# 03-CPU_Core.net
KiCad netlist of a schematic drawn in Altium Designer
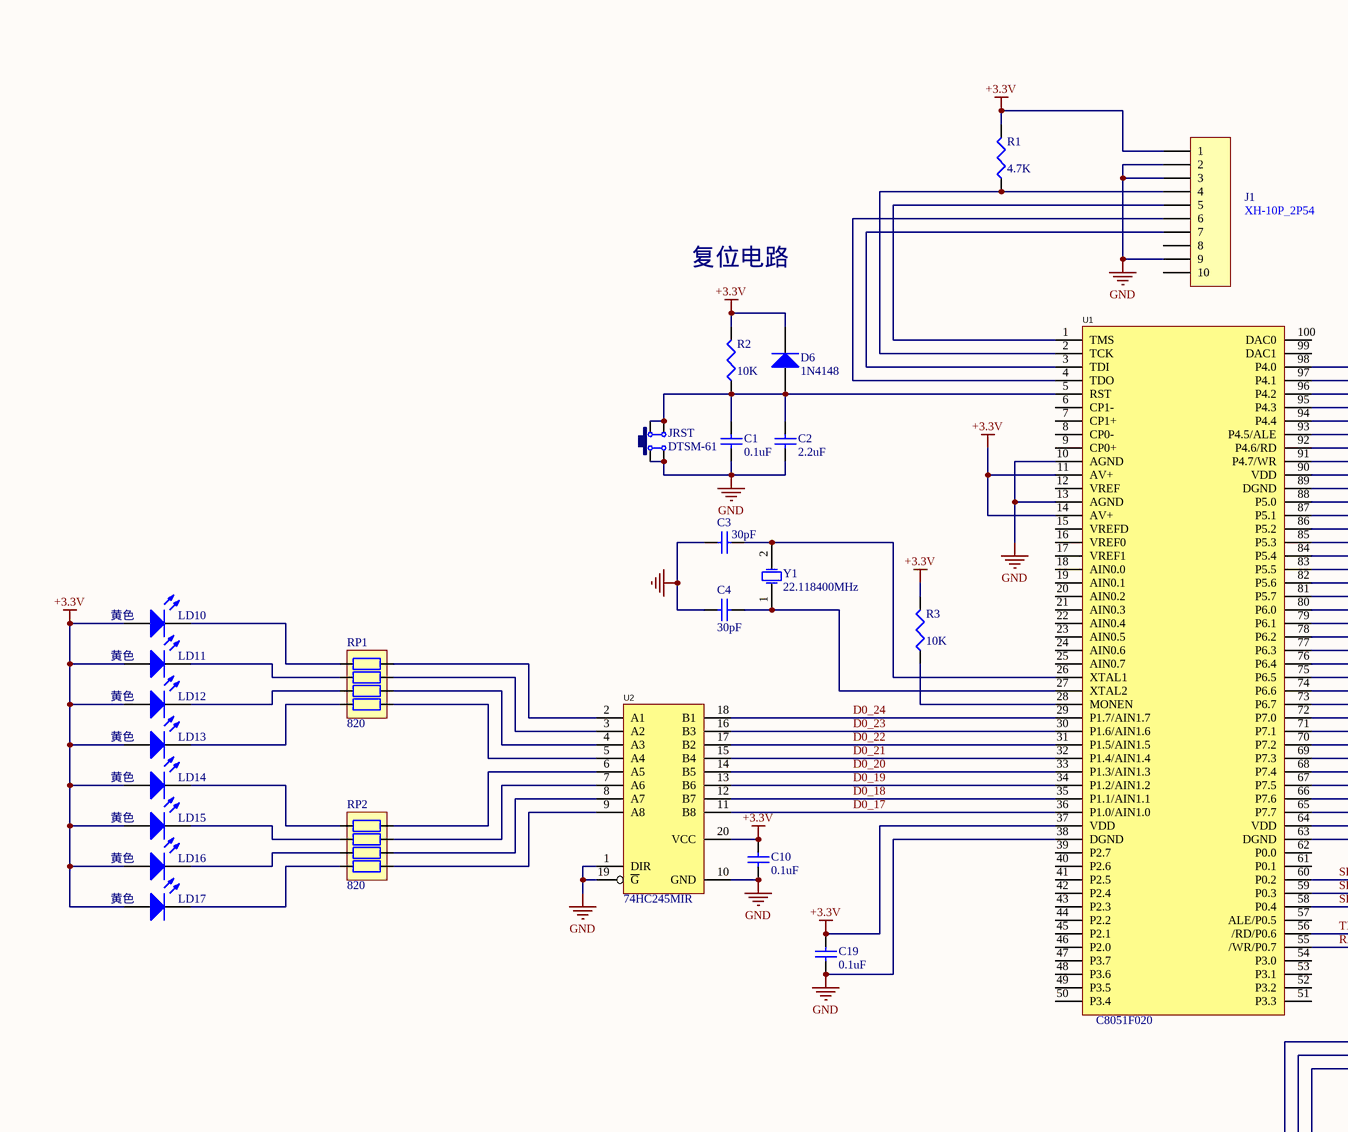
[diagram p0: 03-CPU Core.SchDoc, left]
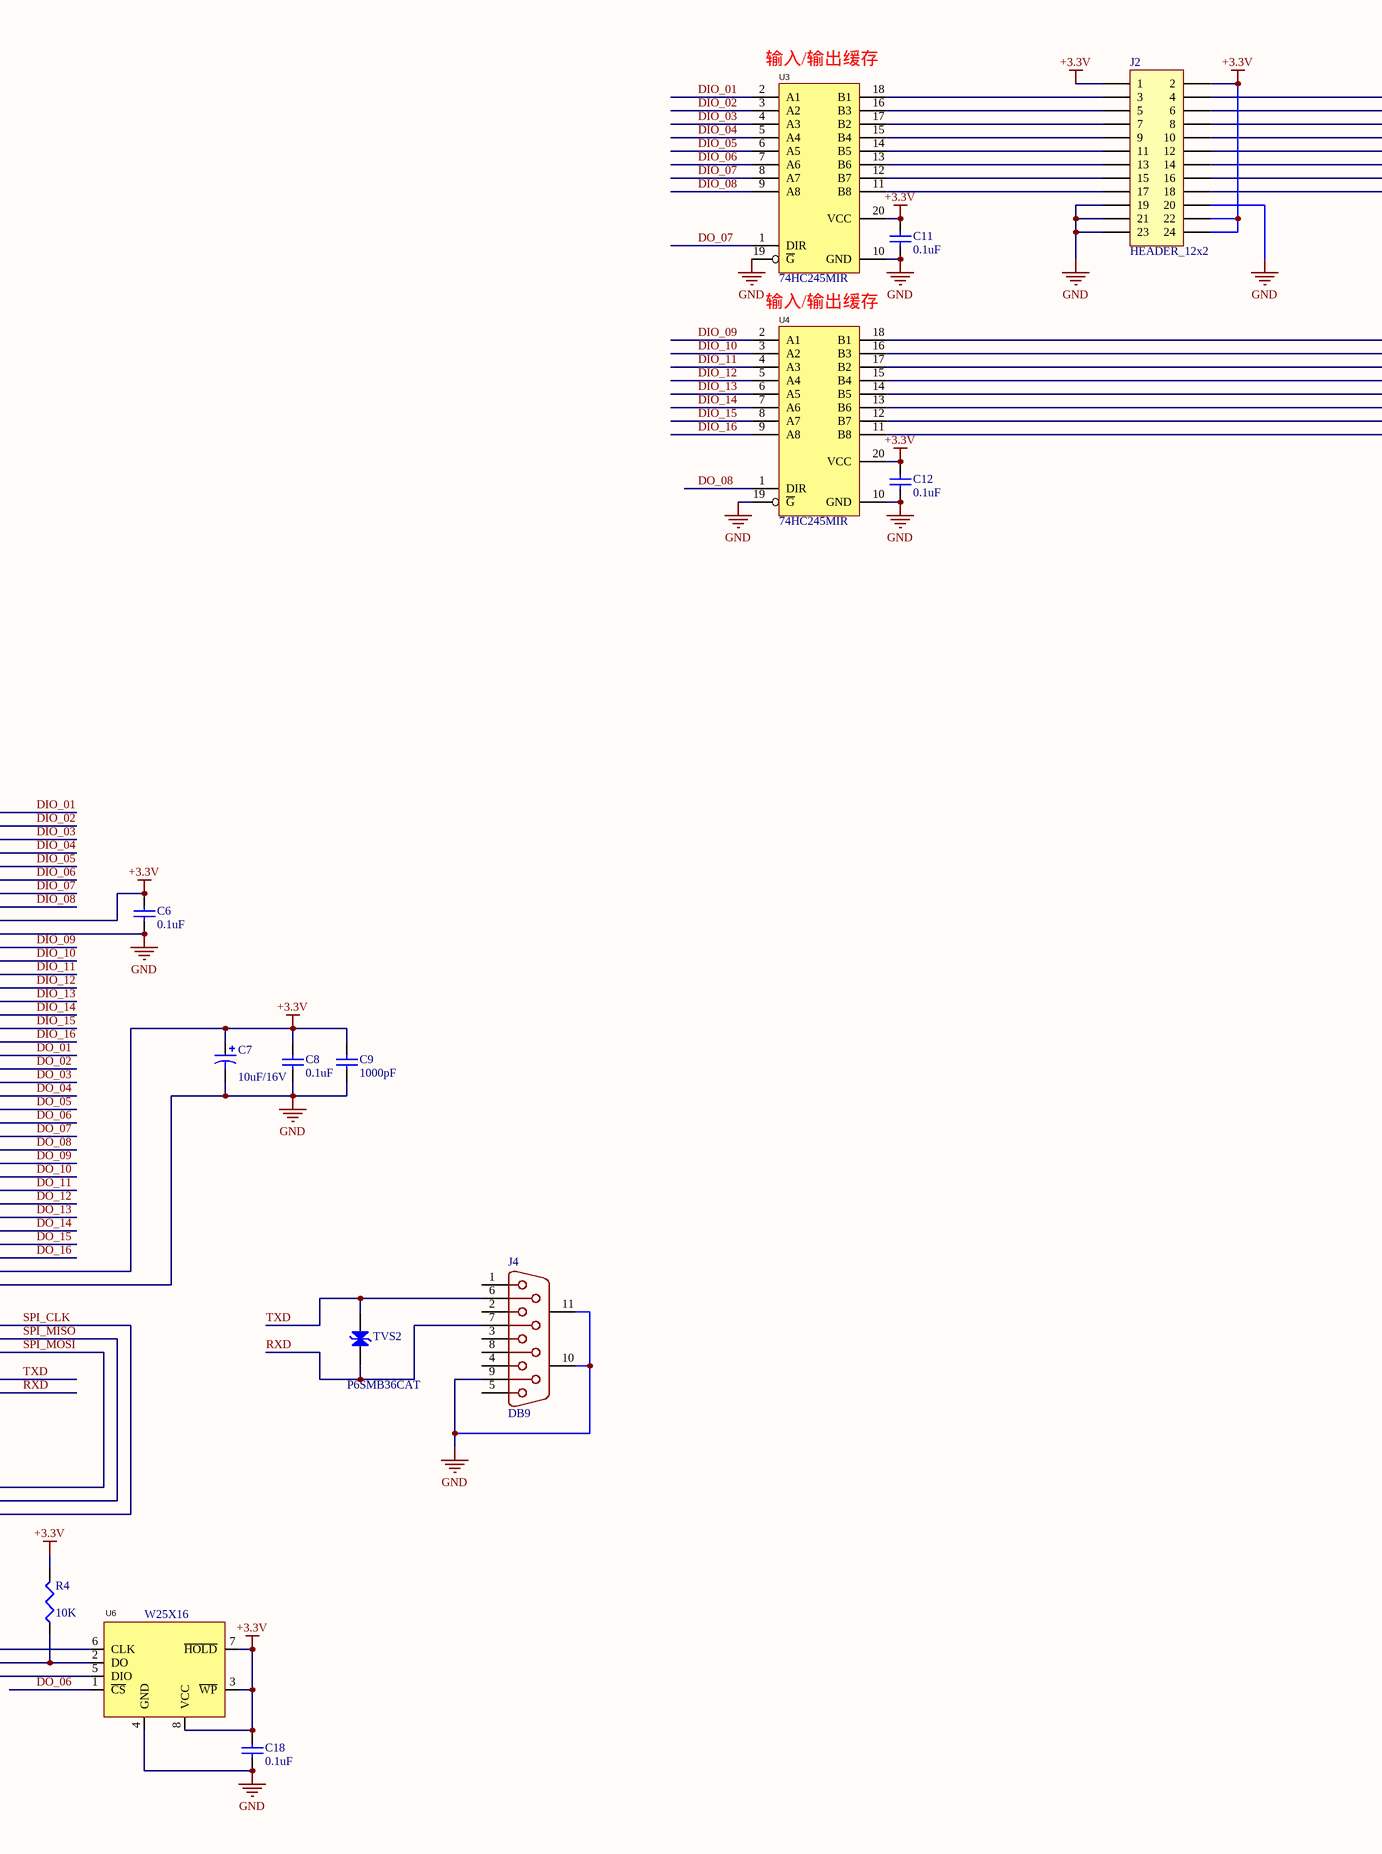
[diagram p1: 03-CPU Core.SchDoc, right]

(export (version "E")
  (design (tool "Eeschema 10.0.6"))
  (components
    (comp (ref "C1")
      (value "0.1uF")
      (footprint "C0805")
      (description "Capacitor")
      (fields (field (name "Comment") "Cap") (field (name "PUBLISHER") "Altium Limited"))
      (libsource (lib "Miscellaneous Devices") (part "Cap"))
    )
    (comp (ref "C2")
      (value "2.2uF")
      (footprint "C0805")
      (description "Capacitor")
      (fields (field (name "Comment") "Cap") (field (name "PUBLISHER") "Altium Limited"))
      (libsource (lib "Miscellaneous Devices") (part "Cap"))
    )
    (comp (ref "C3")
      (value "30pF")
      (footprint "C0805")
      (description "Capacitor")
      (fields (field (name "Comment") "Cap") (field (name "PUBLISHER") "Altium Limited"))
      (libsource (lib "Miscellaneous Devices") (part "Cap"))
    )
    (comp (ref "C4")
      (value "30pF")
      (footprint "C0805")
      (description "Capacitor")
      (fields (field (name "Comment") "Cap") (field (name "PUBLISHER") "Altium Limited"))
      (libsource (lib "Miscellaneous Devices") (part "Cap"))
    )
    (comp (ref "C6")
      (value "0.1uF")
      (footprint "C0805")
      (description "Capacitor")
      (fields (field (name "Comment") "Cap") (field (name "PUBLISHER") "Altium Limited"))
      (libsource (lib "Miscellaneous Devices") (part "Cap"))
    )
    (comp (ref "C7")
      (value "10uF/16V")
      (footprint "C3216")
      (description "Polarized Capacitor (Radial)")
      (fields (field (name "Comment") "Cap Pol1") (field (name "PUBLISHER") "Altium Limited"))
      (libsource (lib "Miscellaneous Devices") (part "Cap Pol1"))
    )
    (comp (ref "C8")
      (value "0.1uF")
      (footprint "C0805")
      (description "Capacitor")
      (fields (field (name "Comment") "Cap") (field (name "PUBLISHER") "Altium Limited"))
      (libsource (lib "Miscellaneous Devices") (part "Cap"))
    )
    (comp (ref "C9")
      (value "1000pF")
      (footprint "C0805")
      (description "Capacitor")
      (fields (field (name "Comment") "Cap") (field (name "PUBLISHER") "Altium Limited"))
      (libsource (lib "Miscellaneous Devices") (part "Cap"))
    )
    (comp (ref "C10")
      (value "0.1uF")
      (footprint "C0805")
      (description "Capacitor")
      (fields (field (name "Comment") "Cap") (field (name "PUBLISHER") "Altium Limited"))
      (libsource (lib "Miscellaneous Devices") (part "Cap"))
    )
    (comp (ref "C11")
      (value "0.1uF")
      (footprint "C0805")
      (description "Capacitor")
      (fields (field (name "Comment") "Cap") (field (name "PUBLISHER") "Altium Limited"))
      (libsource (lib "Miscellaneous Devices") (part "Cap"))
    )
    (comp (ref "C12")
      (value "0.1uF")
      (footprint "C0805")
      (description "Capacitor")
      (fields (field (name "Comment") "Cap") (field (name "PUBLISHER") "Altium Limited"))
      (libsource (lib "Miscellaneous Devices") (part "Cap"))
    )
    (comp (ref "C18")
      (value "0.1uF")
      (footprint "C0805")
      (description "Capacitor")
      (fields (field (name "Comment") "Cap") (field (name "PUBLISHER") "Altium Limited"))
      (libsource (lib "Miscellaneous Devices") (part "Cap"))
    )
    (comp (ref "C19")
      (value "0.1uF")
      (footprint "C0805")
      (description "Capacitor")
      (fields (field (name "Comment") "Cap") (field (name "PUBLISHER") "Altium Limited"))
      (libsource (lib "Miscellaneous Devices") (part "Cap"))
    )
    (comp (ref "D6")
      (value "1N4148")
      (footprint "FR107W")
      (description "Default Diode")
      (fields (field (name "PUBLISHER") "Altium Limited"))
      (libsource (lib "Miscellaneous Devices") (part "Diode"))
    )
    (comp (ref "J1")
      (value "XH-10P_2P54")
      (footprint "XH-10P_2P54")
      (description "Header, 10-Pin")
      (fields (field (name "PUBLISHER") "Altium Limited"))
      (libsource (lib "Miscellaneous Connectors") (part "Header 10"))
    )
    (comp (ref "J2")
      (value "HEADER_12x2")
      (footprint "HEADER_12x2")
      (description "Header, 12-Pin, Dual row")
      (fields (field (name "PUBLISHER") "Altium Limited"))
      (libsource (lib "Miscellaneous Connectors") (part "Header 12X2"))
    )
    (comp (ref "J4") (value "DB9") (footprint "DB9") (libsource (lib "SCHLIB") (part "DB9")))
    (comp (ref "JRST") (value "DTSM-61") (footprint "DISM-61") (libsource (lib "SCHLIB") (part "DTSM-61")))
    (comp (ref "LD10")
      (value "黄色")
      (footprint "LED0805")
      (description "Typical INFRARED GaAs LED")
      (fields (field (name "PUBLISHER") "Altium Limited"))
      (libsource (lib "Miscellaneous Devices") (part "LED0"))
    )
    (comp (ref "LD11")
      (value "黄色")
      (footprint "LED0805")
      (description "Typical INFRARED GaAs LED")
      (fields (field (name "PUBLISHER") "Altium Limited"))
      (libsource (lib "Miscellaneous Devices") (part "LED0"))
    )
    (comp (ref "LD12")
      (value "黄色")
      (footprint "LED0805")
      (description "Typical INFRARED GaAs LED")
      (fields (field (name "PUBLISHER") "Altium Limited"))
      (libsource (lib "Miscellaneous Devices") (part "LED0"))
    )
    (comp (ref "LD13")
      (value "黄色")
      (footprint "LED0805")
      (description "Typical INFRARED GaAs LED")
      (fields (field (name "PUBLISHER") "Altium Limited"))
      (libsource (lib "Miscellaneous Devices") (part "LED0"))
    )
    (comp (ref "LD14")
      (value "黄色")
      (footprint "LED0805")
      (description "Typical INFRARED GaAs LED")
      (fields (field (name "PUBLISHER") "Altium Limited"))
      (libsource (lib "Miscellaneous Devices") (part "LED0"))
    )
    (comp (ref "LD15")
      (value "黄色")
      (footprint "LED0805")
      (description "Typical INFRARED GaAs LED")
      (fields (field (name "PUBLISHER") "Altium Limited"))
      (libsource (lib "Miscellaneous Devices") (part "LED0"))
    )
    (comp (ref "LD16")
      (value "黄色")
      (footprint "LED0805")
      (description "Typical INFRARED GaAs LED")
      (fields (field (name "PUBLISHER") "Altium Limited"))
      (libsource (lib "Miscellaneous Devices") (part "LED0"))
    )
    (comp (ref "LD17")
      (value "黄色")
      (footprint "LED0805")
      (description "Typical INFRARED GaAs LED")
      (fields (field (name "PUBLISHER") "Altium Limited"))
      (libsource (lib "Miscellaneous Devices") (part "LED0"))
    )
    (comp (ref "R1")
      (value "4.7K")
      (footprint "R0805")
      (description "Resistor")
      (fields (field (name "Comment") "Res3") (field (name "PUBLISHER") "Altium Limited"))
      (libsource (lib "Miscellaneous Devices") (part "Res3"))
    )
    (comp (ref "R2")
      (value "10K")
      (footprint "R0805")
      (description "Resistor")
      (fields (field (name "Comment") "Res3") (field (name "PUBLISHER") "Altium Limited"))
      (libsource (lib "Miscellaneous Devices") (part "Res3"))
    )
    (comp (ref "R3")
      (value "10K")
      (footprint "R0805")
      (description "Resistor")
      (fields (field (name "Comment") "Res3") (field (name "PUBLISHER") "Altium Limited"))
      (libsource (lib "Miscellaneous Devices") (part "Res3"))
    )
    (comp (ref "R4")
      (value "10K")
      (footprint "R0805")
      (description "Resistor")
      (fields (field (name "Comment") "Res3") (field (name "PUBLISHER") "Altium Limited"))
      (libsource (lib "Miscellaneous Devices") (part "Res3"))
    )
    (comp (ref "RP1") (value "820") (footprint "RP") (libsource (lib "SCHLIB") (part "RP 820")))
    (comp (ref "RP2") (value "820") (footprint "RP") (libsource (lib "SCHLIB") (part "RP 820")))
    (comp (ref "TVS2") (value "P6SMB36CAT") (footprint "TVS") (libsource (lib "SCHLIB") (part "SMD")))
    (comp (ref "U1")
      (value "C8051F020")
      (footprint "TQFP-100")
      (fields
        (field (name "MANUFACTURER") "SKYWORKS/SILICON LABS(芯科)")
        (field (name "MANUFACTURER PART") "C8051F020-GQR")
      )
      (libsource (lib "C8051F020") (part "C8051F020"))
    )
    (comp (ref "U2")
      (value "74HC245MIR")
      (footprint "SSOP-20")
      (fields (field (name "MANUFACTURER") "Nexperia(安世)") (field (name "MANUFACTURER PART") "74HC245PW,118"))
      (libsource (lib "C8051F020") (part "74HC245MIR"))
    )
    (comp (ref "U3")
      (value "74HC245MIR")
      (footprint "SSOP-20")
      (fields (field (name "MANUFACTURER") "Nexperia(安世)") (field (name "MANUFACTURER PART") "74HC245PW,118"))
      (libsource (lib "C8051F020") (part "74HC245MIR"))
    )
    (comp (ref "U4")
      (value "74HC245MIR")
      (footprint "SSOP-20")
      (fields (field (name "MANUFACTURER") "Nexperia(安世)") (field (name "MANUFACTURER PART") "74HC245PW,118"))
      (libsource (lib "C8051F020") (part "74HC245MIR"))
    )
    (comp (ref "U6")
      (value "W25X16")
      (footprint "SOIC-8")
      (fields (field (name "MANUFACTURER") "WINBOND(华邦)") (field (name "MANUFACTURER PART") "W25X16VSSIG"))
      (libsource (lib "C8051F020") (part "W25X16"))
    )
    (comp (ref "Y1")
      (value "22.118400MHz")
      (footprint "HC-49")
      (description "Crystal Oscillator")
      (fields (field (name "PUBLISHER") "Altium Limited"))
      (libsource (lib "Miscellaneous Devices") (part "XTAL"))
    )
  )
  (nets
    (net (code "1") (name "+3.3V") (class "Default")
      (node (ref "C10") (pin "2") (pinfunction "2_2") (pintype "passive"))
      (node (ref "C11") (pin "2") (pinfunction "2_2") (pintype "passive"))
      (node (ref "C12") (pin "2") (pinfunction "2_2") (pintype "passive"))
      (node (ref "C18") (pin "2") (pinfunction "2_2") (pintype "passive"))
      (node (ref "C19") (pin "2") (pinfunction "2_2") (pintype "passive"))
      (node (ref "C6") (pin "2") (pinfunction "2_2") (pintype "passive"))
      (node (ref "C7") (pin "1") (pinfunction "1_1") (pintype "passive"))
      (node (ref "C8") (pin "2") (pinfunction "2_2") (pintype "passive"))
      (node (ref "C9") (pin "2") (pinfunction "2_2") (pintype "passive"))
      (node (ref "D6") (pin "2") (pinfunction "K_2") (pintype "passive"))
      (node (ref "J1") (pin "1") (pinfunction "1_1") (pintype "passive"))
      (node (ref "J2") (pin "1") (pinfunction "1_1") (pintype "passive"))
      (node (ref "J2") (pin "2") (pinfunction "2_2") (pintype "passive"))
      (node (ref "J2") (pin "22") (pinfunction "22_22") (pintype "passive"))
      (node (ref "J2") (pin "24") (pinfunction "24_24") (pintype "passive"))
      (node (ref "LD10") (pin "1") (pinfunction "A_1") (pintype "passive"))
      (node (ref "LD11") (pin "1") (pinfunction "A_1") (pintype "passive"))
      (node (ref "LD12") (pin "1") (pinfunction "A_1") (pintype "passive"))
      (node (ref "LD13") (pin "1") (pinfunction "A_1") (pintype "passive"))
      (node (ref "LD14") (pin "1") (pinfunction "A_1") (pintype "passive"))
      (node (ref "LD15") (pin "1") (pinfunction "A_1") (pintype "passive"))
      (node (ref "LD16") (pin "1") (pinfunction "A_1") (pintype "passive"))
      (node (ref "LD17") (pin "1") (pinfunction "A_1") (pintype "passive"))
      (node (ref "R1") (pin "2") (pinfunction "2_2") (pintype "passive"))
      (node (ref "R2") (pin "2") (pinfunction "2_2") (pintype "passive"))
      (node (ref "R3") (pin "2") (pinfunction "2_2") (pintype "passive"))
      (node (ref "R4") (pin "2") (pinfunction "2_2") (pintype "passive"))
      (node (ref "U1") (pin "11") (pinfunction "AV+_11") (pintype "passive"))
      (node (ref "U1") (pin "14") (pinfunction "AV+_14") (pintype "passive"))
      (node (ref "U1") (pin "37") (pinfunction "VDD_37") (pintype "passive"))
      (node (ref "U1") (pin "64") (pinfunction "VDD_64") (pintype "passive"))
      (node (ref "U1") (pin "90") (pinfunction "VDD_90") (pintype "passive"))
      (node (ref "U2") (pin "20") (pinfunction "VCC_20") (pintype "passive"))
      (node (ref "U3") (pin "20") (pinfunction "VCC_20") (pintype "passive"))
      (node (ref "U4") (pin "20") (pinfunction "VCC_20") (pintype "passive"))
      (node (ref "U6") (pin "3") (pinfunction "~{WP}_3") (pintype "passive"))
      (node (ref "U6") (pin "7") (pinfunction "~{HOLD}_7") (pintype "passive"))
      (node (ref "U6") (pin "8") (pinfunction "VCC_8") (pintype "passive"))
    )
    (net (code "2") (name "/D0_17") (class "Default")
      (node (ref "U1") (pin "36") (pinfunction "P1.0/AIN1.0_36") (pintype "passive"))
      (node (ref "U2") (pin "11") (pinfunction "B8_11") (pintype "passive"))
    )
    (net (code "3") (name "/D0_18") (class "Default")
      (node (ref "U1") (pin "35") (pinfunction "P1.1/AIN1.1_35") (pintype "passive"))
      (node (ref "U2") (pin "12") (pinfunction "B7_12") (pintype "passive"))
    )
    (net (code "4") (name "/D0_19") (class "Default")
      (node (ref "U1") (pin "34") (pinfunction "P1.2/AIN1.2_34") (pintype "passive"))
      (node (ref "U2") (pin "13") (pinfunction "B6_13") (pintype "passive"))
    )
    (net (code "5") (name "/D0_20") (class "Default")
      (node (ref "U1") (pin "33") (pinfunction "P1.3/AIN1.3_33") (pintype "passive"))
      (node (ref "U2") (pin "14") (pinfunction "B5_14") (pintype "passive"))
    )
    (net (code "6") (name "/D0_21") (class "Default")
      (node (ref "U1") (pin "32") (pinfunction "P1.4/AIN1.4_32") (pintype "passive"))
      (node (ref "U2") (pin "15") (pinfunction "B4_15") (pintype "passive"))
    )
    (net (code "7") (name "/D0_22") (class "Default")
      (node (ref "U1") (pin "31") (pinfunction "P1.5/AIN1.5_31") (pintype "passive"))
      (node (ref "U2") (pin "17") (pinfunction "B2_17") (pintype "passive"))
    )
    (net (code "8") (name "/D0_23") (class "Default")
      (node (ref "U1") (pin "30") (pinfunction "P1.6/AIN1.6_30") (pintype "passive"))
      (node (ref "U2") (pin "16") (pinfunction "B3_16") (pintype "passive"))
    )
    (net (code "9") (name "/D0_24") (class "Default")
      (node (ref "U1") (pin "29") (pinfunction "P1.7/AIN1.7_29") (pintype "passive"))
      (node (ref "U2") (pin "18") (pinfunction "B1_18") (pintype "passive"))
    )
    (net (code "10") (name "/DIO_01") (class "Default")
      (node (ref "U1") (pin "98") (pinfunction "P4.0_98") (pintype "passive"))
      (node (ref "U3") (pin "2") (pinfunction "A1_2") (pintype "passive"))
    )
    (net (code "11") (name "/DIO_02") (class "Default")
      (node (ref "U1") (pin "97") (pinfunction "P4.1_97") (pintype "passive"))
      (node (ref "U3") (pin "3") (pinfunction "A2_3") (pintype "passive"))
    )
    (net (code "12") (name "/DIO_03") (class "Default")
      (node (ref "U1") (pin "96") (pinfunction "P4.2_96") (pintype "passive"))
      (node (ref "U3") (pin "4") (pinfunction "A3_4") (pintype "passive"))
    )
    (net (code "13") (name "/DIO_04") (class "Default")
      (node (ref "U1") (pin "95") (pinfunction "P4.3_95") (pintype "passive"))
      (node (ref "U3") (pin "5") (pinfunction "A4_5") (pintype "passive"))
    )
    (net (code "14") (name "/DIO_05") (class "Default")
      (node (ref "U1") (pin "94") (pinfunction "P4.4_94") (pintype "passive"))
      (node (ref "U3") (pin "6") (pinfunction "A5_6") (pintype "passive"))
    )
    (net (code "15") (name "/DIO_06") (class "Default")
      (node (ref "U1") (pin "93") (pinfunction "P4.5/ALE_93") (pintype "passive"))
      (node (ref "U3") (pin "7") (pinfunction "A6_7") (pintype "passive"))
    )
    (net (code "16") (name "/DIO_07") (class "Default")
      (node (ref "U1") (pin "92") (pinfunction "P4.6/RD_92") (pintype "passive"))
      (node (ref "U3") (pin "8") (pinfunction "A7_8") (pintype "passive"))
    )
    (net (code "17") (name "/DIO_08") (class "Default")
      (node (ref "U1") (pin "91") (pinfunction "P4.7/WR_91") (pintype "passive"))
      (node (ref "U3") (pin "9") (pinfunction "A8_9") (pintype "passive"))
    )
    (net (code "18") (name "/DIO_09") (class "Default")
      (node (ref "U1") (pin "88") (pinfunction "P5.0_88") (pintype "passive"))
      (node (ref "U4") (pin "2") (pinfunction "A1_2") (pintype "passive"))
    )
    (net (code "19") (name "/DIO_10") (class "Default")
      (node (ref "U1") (pin "87") (pinfunction "P5.1_87") (pintype "passive"))
      (node (ref "U4") (pin "3") (pinfunction "A2_3") (pintype "passive"))
    )
    (net (code "20") (name "/DIO_11") (class "Default")
      (node (ref "U1") (pin "86") (pinfunction "P5.2_86") (pintype "passive"))
      (node (ref "U4") (pin "4") (pinfunction "A3_4") (pintype "passive"))
    )
    (net (code "21") (name "/DIO_12") (class "Default")
      (node (ref "U1") (pin "85") (pinfunction "P5.3_85") (pintype "passive"))
      (node (ref "U4") (pin "5") (pinfunction "A4_5") (pintype "passive"))
    )
    (net (code "22") (name "/DIO_13") (class "Default")
      (node (ref "U1") (pin "84") (pinfunction "P5.4_84") (pintype "passive"))
      (node (ref "U4") (pin "6") (pinfunction "A5_6") (pintype "passive"))
    )
    (net (code "23") (name "/DIO_14") (class "Default")
      (node (ref "U1") (pin "83") (pinfunction "P5.5_83") (pintype "passive"))
      (node (ref "U4") (pin "7") (pinfunction "A6_7") (pintype "passive"))
    )
    (net (code "24") (name "/DIO_15") (class "Default")
      (node (ref "U1") (pin "82") (pinfunction "P5.6_82") (pintype "passive"))
      (node (ref "U4") (pin "8") (pinfunction "A7_8") (pintype "passive"))
    )
    (net (code "25") (name "/DIO_16") (class "Default")
      (node (ref "U1") (pin "81") (pinfunction "P5.7_81") (pintype "passive"))
      (node (ref "U4") (pin "9") (pinfunction "A8_9") (pintype "passive"))
    )
    (net (code "26") (name "/DO_01") (class "Default")
      (node (ref "U1") (pin "80") (pinfunction "P6.0_80") (pintype "passive"))
    )
    (net (code "27") (name "/DO_02") (class "Default")
      (node (ref "U1") (pin "79") (pinfunction "P6.1_79") (pintype "passive"))
    )
    (net (code "28") (name "/DO_03") (class "Default")
      (node (ref "U1") (pin "78") (pinfunction "P6.2_78") (pintype "passive"))
    )
    (net (code "29") (name "/DO_04") (class "Default")
      (node (ref "U1") (pin "77") (pinfunction "P6.3_77") (pintype "passive"))
    )
    (net (code "30") (name "/DO_05") (class "Default")
      (node (ref "U1") (pin "76") (pinfunction "P6.4_76") (pintype "passive"))
    )
    (net (code "31") (name "/DO_06") (class "Default")
      (node (ref "U1") (pin "75") (pinfunction "P6.5_75") (pintype "passive"))
      (node (ref "U6") (pin "1") (pinfunction "~{CS}_1") (pintype "passive"))
    )
    (net (code "32") (name "/DO_07") (class "Default")
      (node (ref "U1") (pin "74") (pinfunction "P6.6_74") (pintype "passive"))
      (node (ref "U3") (pin "1") (pinfunction "DIR_1") (pintype "passive"))
    )
    (net (code "33") (name "/DO_08") (class "Default")
      (node (ref "U1") (pin "73") (pinfunction "P6.7_73") (pintype "passive"))
      (node (ref "U4") (pin "1") (pinfunction "DIR_1") (pintype "passive"))
    )
    (net (code "34") (name "/DO_09") (class "Default")
      (node (ref "U1") (pin "72") (pinfunction "P7.0_72") (pintype "passive"))
    )
    (net (code "35") (name "/DO_10") (class "Default")
      (node (ref "U1") (pin "71") (pinfunction "P7.1_71") (pintype "passive"))
    )
    (net (code "36") (name "/DO_11") (class "Default")
      (node (ref "U1") (pin "70") (pinfunction "P7.2_70") (pintype "passive"))
    )
    (net (code "37") (name "/DO_12") (class "Default")
      (node (ref "U1") (pin "69") (pinfunction "P7.3_69") (pintype "passive"))
    )
    (net (code "38") (name "/DO_13") (class "Default")
      (node (ref "U1") (pin "68") (pinfunction "P7.4_68") (pintype "passive"))
    )
    (net (code "39") (name "/DO_14") (class "Default")
      (node (ref "U1") (pin "67") (pinfunction "P7.5_67") (pintype "passive"))
    )
    (net (code "40") (name "/DO_15") (class "Default")
      (node (ref "U1") (pin "66") (pinfunction "P7.6_66") (pintype "passive"))
    )
    (net (code "41") (name "/DO_16") (class "Default")
      (node (ref "U1") (pin "65") (pinfunction "P7.7_65") (pintype "passive"))
    )
    (net (code "42") (name "/RXD") (class "Default")
      (node (ref "J4") (pin "7") (pinfunction "7_7") (pintype "passive"))
      (node (ref "TVS2") (pin "2") (pinfunction "K_2") (pintype "passive"))
      (node (ref "U1") (pin "55") (pinfunction "/WR/P0.7_55") (pintype "passive"))
    )
    (net (code "43") (name "/SPI_CLK") (class "Default")
      (node (ref "U1") (pin "60") (pinfunction "P0.2_60") (pintype "passive"))
      (node (ref "U6") (pin "6") (pinfunction "CLK_6") (pintype "passive"))
    )
    (net (code "44") (name "/SPI_MISO") (class "Default")
      (node (ref "R4") (pin "1") (pinfunction "1_1") (pintype "passive"))
      (node (ref "U1") (pin "59") (pinfunction "P0.3_59") (pintype "passive"))
      (node (ref "U6") (pin "2") (pinfunction "DO_2") (pintype "passive"))
    )
    (net (code "45") (name "/SPI_MOSI") (class "Default")
      (node (ref "U1") (pin "58") (pinfunction "P0.4_58") (pintype "passive"))
      (node (ref "U6") (pin "5") (pinfunction "DIO_5") (pintype "passive"))
    )
    (net (code "46") (name "/TXD") (class "Default")
      (node (ref "J4") (pin "6") (pinfunction "6_6") (pintype "passive"))
      (node (ref "TVS2") (pin "1") (pinfunction "A_1") (pintype "passive"))
      (node (ref "U1") (pin "56") (pinfunction "/RD/P0.6_56") (pintype "passive"))
    )
    (net (code "47") (name "GND") (class "Default")
      (node (ref "C1") (pin "2") (pinfunction "2_2") (pintype "passive"))
      (node (ref "C10") (pin "1") (pinfunction "1_1") (pintype "passive"))
      (node (ref "C11") (pin "1") (pinfunction "1_1") (pintype "passive"))
      (node (ref "C12") (pin "1") (pinfunction "1_1") (pintype "passive"))
      (node (ref "C18") (pin "1") (pinfunction "1_1") (pintype "passive"))
      (node (ref "C19") (pin "1") (pinfunction "1_1") (pintype "passive"))
      (node (ref "C2") (pin "2") (pinfunction "2_2") (pintype "passive"))
      (node (ref "C3") (pin "1") (pinfunction "1_1") (pintype "passive"))
      (node (ref "C4") (pin "1") (pinfunction "1_1") (pintype "passive"))
      (node (ref "C6") (pin "1") (pinfunction "1_1") (pintype "passive"))
      (node (ref "C7") (pin "2") (pinfunction "2_2") (pintype "passive"))
      (node (ref "C8") (pin "1") (pinfunction "1_1") (pintype "passive"))
      (node (ref "C9") (pin "1") (pinfunction "1_1") (pintype "passive"))
      (node (ref "J1") (pin "2") (pinfunction "2_2") (pintype "passive"))
      (node (ref "J1") (pin "3") (pinfunction "3_3") (pintype "passive"))
      (node (ref "J1") (pin "9") (pinfunction "9_9") (pintype "passive"))
      (node (ref "J2") (pin "19") (pinfunction "19_19") (pintype "passive"))
      (node (ref "J2") (pin "20") (pinfunction "20_20") (pintype "passive"))
      (node (ref "J2") (pin "21") (pinfunction "21_21") (pintype "passive"))
      (node (ref "J2") (pin "23") (pinfunction "23_23") (pintype "passive"))
      (node (ref "J4") (pin "10") (pinfunction "MH1_10") (pintype "passive"))
      (node (ref "J4") (pin "11") (pinfunction "MH2_11") (pintype "passive"))
      (node (ref "J4") (pin "9") (pinfunction "9_9") (pintype "passive"))
      (node (ref "JRST") (pin "1") (pinfunction "1_1") (pintype "passive"))
      (node (ref "JRST") (pin "4") (pinfunction "4_4") (pintype "passive"))
      (node (ref "U1") (pin "10") (pinfunction "AGND_10") (pintype "passive"))
      (node (ref "U1") (pin "13") (pinfunction "AGND_13") (pintype "passive"))
      (node (ref "U1") (pin "38") (pinfunction "DGND_38") (pintype "passive"))
      (node (ref "U1") (pin "63") (pinfunction "DGND_63") (pintype "passive"))
      (node (ref "U1") (pin "89") (pinfunction "DGND_89") (pintype "passive"))
      (node (ref "U2") (pin "1") (pinfunction "DIR_1") (pintype "passive"))
      (node (ref "U2") (pin "10") (pinfunction "GND_10") (pintype "passive"))
      (node (ref "U2") (pin "19") (pinfunction "~{G}_19") (pintype "passive"))
      (node (ref "U3") (pin "10") (pinfunction "GND_10") (pintype "passive"))
      (node (ref "U3") (pin "19") (pinfunction "~{G}_19") (pintype "passive"))
      (node (ref "U4") (pin "10") (pinfunction "GND_10") (pintype "passive"))
      (node (ref "U4") (pin "19") (pinfunction "~{G}_19") (pintype "passive"))
      (node (ref "U6") (pin "4") (pinfunction "GND_4") (pintype "passive"))
    )
    (net (code "48") (name "Net-(D6-A)") (class "Default")
      (node (ref "C1") (pin "1") (pinfunction "1_1") (pintype "passive"))
      (node (ref "C2") (pin "1") (pinfunction "1_1") (pintype "passive"))
      (node (ref "D6") (pin "1") (pinfunction "A_1") (pintype "passive"))
      (node (ref "JRST") (pin "2") (pinfunction "2_2") (pintype "passive"))
      (node (ref "JRST") (pin "3") (pinfunction "3_3") (pintype "passive"))
      (node (ref "R2") (pin "1") (pinfunction "1_1") (pintype "passive"))
      (node (ref "U1") (pin "5") (pinfunction "RST_5") (pintype "passive"))
    )
    (net (code "49") (name "Net-(LD10-K)") (class "Default")
      (node (ref "LD10") (pin "2") (pinfunction "K_2") (pintype "passive"))
      (node (ref "RP1") (pin "1") (pinfunction "1_1") (pintype "passive"))
    )
    (net (code "50") (name "Net-(LD11-K)") (class "Default")
      (node (ref "LD11") (pin "2") (pinfunction "K_2") (pintype "passive"))
      (node (ref "RP1") (pin "2") (pinfunction "2_2") (pintype "passive"))
    )
    (net (code "51") (name "Net-(LD12-K)") (class "Default")
      (node (ref "LD12") (pin "2") (pinfunction "K_2") (pintype "passive"))
      (node (ref "RP1") (pin "3") (pinfunction "3_3") (pintype "passive"))
    )
    (net (code "52") (name "Net-(LD13-K)") (class "Default")
      (node (ref "LD13") (pin "2") (pinfunction "K_2") (pintype "passive"))
      (node (ref "RP1") (pin "4") (pinfunction "4_4") (pintype "passive"))
    )
    (net (code "53") (name "Net-(LD14-K)") (class "Default")
      (node (ref "LD14") (pin "2") (pinfunction "K_2") (pintype "passive"))
      (node (ref "RP2") (pin "1") (pinfunction "1_1") (pintype "passive"))
    )
    (net (code "54") (name "Net-(LD15-K)") (class "Default")
      (node (ref "LD15") (pin "2") (pinfunction "K_2") (pintype "passive"))
      (node (ref "RP2") (pin "2") (pinfunction "2_2") (pintype "passive"))
    )
    (net (code "55") (name "Net-(LD16-K)") (class "Default")
      (node (ref "LD16") (pin "2") (pinfunction "K_2") (pintype "passive"))
      (node (ref "RP2") (pin "3") (pinfunction "3_3") (pintype "passive"))
    )
    (net (code "56") (name "Net-(LD17-K)") (class "Default")
      (node (ref "LD17") (pin "2") (pinfunction "K_2") (pintype "passive"))
      (node (ref "RP2") (pin "4") (pinfunction "4_4") (pintype "passive"))
    )
    (net (code "57") (name "Net-(U1-MONEN)") (class "Default")
      (node (ref "R3") (pin "1") (pinfunction "1_1") (pintype "passive"))
      (node (ref "U1") (pin "28") (pinfunction "MONEN_28") (pintype "passive"))
    )
    (net (code "58") (name "Net-(U1-TCK)") (class "Default")
      (node (ref "J1") (pin "4") (pinfunction "4_4") (pintype "passive"))
      (node (ref "R1") (pin "1") (pinfunction "1_1") (pintype "passive"))
      (node (ref "U1") (pin "2") (pinfunction "TCK_2") (pintype "passive"))
    )
    (net (code "59") (name "Net-(U1-TDI)") (class "Default")
      (node (ref "J1") (pin "7") (pinfunction "7_7") (pintype "passive"))
      (node (ref "U1") (pin "3") (pinfunction "TDI_3") (pintype "passive"))
    )
    (net (code "60") (name "Net-(U1-TDO)") (class "Default")
      (node (ref "J1") (pin "6") (pinfunction "6_6") (pintype "passive"))
      (node (ref "U1") (pin "4") (pinfunction "TDO_4") (pintype "passive"))
    )
    (net (code "61") (name "Net-(U1-TMS)") (class "Default")
      (node (ref "J1") (pin "5") (pinfunction "5_5") (pintype "passive"))
      (node (ref "U1") (pin "1") (pinfunction "TMS_1") (pintype "passive"))
    )
    (net (code "62") (name "Net-(U1-XTAL1)") (class "Default")
      (node (ref "C3") (pin "2") (pinfunction "2_2") (pintype "passive"))
      (node (ref "U1") (pin "26") (pinfunction "XTAL1_26") (pintype "passive"))
      (node (ref "Y1") (pin "2") (pinfunction "OSC2_2") (pintype "passive"))
    )
    (net (code "63") (name "Net-(U1-XTAL2)") (class "Default")
      (node (ref "C4") (pin "2") (pinfunction "2_2") (pintype "passive"))
      (node (ref "U1") (pin "27") (pinfunction "XTAL2_27") (pintype "passive"))
      (node (ref "Y1") (pin "1") (pinfunction "OSC1_1") (pintype "passive"))
    )
    (net (code "64") (name "Net-(U2-A1)") (class "Default")
      (node (ref "RP1") (pin "8") (pinfunction "8_8") (pintype "passive"))
      (node (ref "U2") (pin "2") (pinfunction "A1_2") (pintype "passive"))
    )
    (net (code "65") (name "Net-(U2-A2)") (class "Default")
      (node (ref "RP1") (pin "7") (pinfunction "7_7") (pintype "passive"))
      (node (ref "U2") (pin "3") (pinfunction "A2_3") (pintype "passive"))
    )
    (net (code "66") (name "Net-(U2-A3)") (class "Default")
      (node (ref "RP1") (pin "6") (pinfunction "6_6") (pintype "passive"))
      (node (ref "U2") (pin "4") (pinfunction "A3_4") (pintype "passive"))
    )
    (net (code "67") (name "Net-(U2-A4)") (class "Default")
      (node (ref "RP1") (pin "5") (pinfunction "5_5") (pintype "passive"))
      (node (ref "U2") (pin "5") (pinfunction "A4_5") (pintype "passive"))
    )
    (net (code "68") (name "Net-(U2-A5)") (class "Default")
      (node (ref "RP2") (pin "8") (pinfunction "8_8") (pintype "passive"))
      (node (ref "U2") (pin "6") (pinfunction "A5_6") (pintype "passive"))
    )
    (net (code "69") (name "Net-(U2-A6)") (class "Default")
      (node (ref "RP2") (pin "7") (pinfunction "7_7") (pintype "passive"))
      (node (ref "U2") (pin "7") (pinfunction "A6_7") (pintype "passive"))
    )
    (net (code "70") (name "Net-(U2-A7)") (class "Default")
      (node (ref "RP2") (pin "6") (pinfunction "6_6") (pintype "passive"))
      (node (ref "U2") (pin "8") (pinfunction "A7_8") (pintype "passive"))
    )
    (net (code "71") (name "Net-(U2-A8)") (class "Default")
      (node (ref "RP2") (pin "5") (pinfunction "5_5") (pintype "passive"))
      (node (ref "U2") (pin "9") (pinfunction "A8_9") (pintype "passive"))
    )
    (net (code "72") (name "Net-(U3-B1)") (class "Default")
      (node (ref "J2") (pin "3") (pinfunction "3_3") (pintype "passive"))
      (node (ref "U3") (pin "18") (pinfunction "B1_18") (pintype "passive"))
    )
    (net (code "73") (name "Net-(U3-B2)") (class "Default")
      (node (ref "J2") (pin "7") (pinfunction "7_7") (pintype "passive"))
      (node (ref "U3") (pin "17") (pinfunction "B2_17") (pintype "passive"))
    )
    (net (code "74") (name "Net-(U3-B3)") (class "Default")
      (node (ref "J2") (pin "5") (pinfunction "5_5") (pintype "passive"))
      (node (ref "U3") (pin "16") (pinfunction "B3_16") (pintype "passive"))
    )
    (net (code "75") (name "Net-(U3-B4)") (class "Default")
      (node (ref "J2") (pin "9") (pinfunction "9_9") (pintype "passive"))
      (node (ref "U3") (pin "15") (pinfunction "B4_15") (pintype "passive"))
    )
    (net (code "76") (name "Net-(U3-B5)") (class "Default")
      (node (ref "J2") (pin "11") (pinfunction "11_11") (pintype "passive"))
      (node (ref "U3") (pin "14") (pinfunction "B5_14") (pintype "passive"))
    )
    (net (code "77") (name "Net-(U3-B6)") (class "Default")
      (node (ref "J2") (pin "13") (pinfunction "13_13") (pintype "passive"))
      (node (ref "U3") (pin "13") (pinfunction "B6_13") (pintype "passive"))
    )
    (net (code "78") (name "Net-(U3-B7)") (class "Default")
      (node (ref "J2") (pin "15") (pinfunction "15_15") (pintype "passive"))
      (node (ref "U3") (pin "12") (pinfunction "B7_12") (pintype "passive"))
    )
    (net (code "79") (name "Net-(U3-B8)") (class "Default")
      (node (ref "J2") (pin "17") (pinfunction "17_17") (pintype "passive"))
      (node (ref "U3") (pin "11") (pinfunction "B8_11") (pintype "passive"))
    )
    (net (code "80") (name "Net-(U4-B1)") (class "Default")
      (node (ref "J2") (pin "4") (pinfunction "4_4") (pintype "passive"))
      (node (ref "U4") (pin "18") (pinfunction "B1_18") (pintype "passive"))
    )
    (net (code "81") (name "Net-(U4-B2)") (class "Default")
      (node (ref "J2") (pin "8") (pinfunction "8_8") (pintype "passive"))
      (node (ref "U4") (pin "17") (pinfunction "B2_17") (pintype "passive"))
    )
    (net (code "82") (name "Net-(U4-B3)") (class "Default")
      (node (ref "J2") (pin "6") (pinfunction "6_6") (pintype "passive"))
      (node (ref "U4") (pin "16") (pinfunction "B3_16") (pintype "passive"))
    )
    (net (code "83") (name "Net-(U4-B4)") (class "Default")
      (node (ref "J2") (pin "10") (pinfunction "10_10") (pintype "passive"))
      (node (ref "U4") (pin "15") (pinfunction "B4_15") (pintype "passive"))
    )
    (net (code "84") (name "Net-(U4-B5)") (class "Default")
      (node (ref "J2") (pin "12") (pinfunction "12_12") (pintype "passive"))
      (node (ref "U4") (pin "14") (pinfunction "B5_14") (pintype "passive"))
    )
    (net (code "85") (name "Net-(U4-B6)") (class "Default")
      (node (ref "J2") (pin "14") (pinfunction "14_14") (pintype "passive"))
      (node (ref "U4") (pin "13") (pinfunction "B6_13") (pintype "passive"))
    )
    (net (code "86") (name "Net-(U4-B7)") (class "Default")
      (node (ref "J2") (pin "16") (pinfunction "16_16") (pintype "passive"))
      (node (ref "U4") (pin "12") (pinfunction "B7_12") (pintype "passive"))
    )
    (net (code "87") (name "Net-(U4-B8)") (class "Default")
      (node (ref "J2") (pin "18") (pinfunction "18_18") (pintype "passive"))
      (node (ref "U4") (pin "11") (pinfunction "B8_11") (pintype "passive"))
    )
    (net (code "88") (name "unconnected-(J1-Pad8)") (class "Default")
      (node (ref "J1") (pin "8") (pinfunction "8_8") (pintype "passive"))
    )
    (net (code "89") (name "unconnected-(J1-Pad10)") (class "Default")
      (node (ref "J1") (pin "10") (pinfunction "10_10") (pintype "passive"))
    )
    (net (code "90") (name "unconnected-(J4-Pad1)") (class "Default")
      (node (ref "J4") (pin "1") (pinfunction "1_1") (pintype "passive"))
    )
    (net (code "91") (name "unconnected-(J4-Pad2)") (class "Default")
      (node (ref "J4") (pin "2") (pinfunction "2_2") (pintype "passive"))
    )
    (net (code "92") (name "unconnected-(J4-Pad3)") (class "Default")
      (node (ref "J4") (pin "3") (pinfunction "3_3") (pintype "passive"))
    )
    (net (code "93") (name "unconnected-(J4-Pad4)") (class "Default")
      (node (ref "J4") (pin "4") (pinfunction "4_4") (pintype "passive"))
    )
    (net (code "94") (name "unconnected-(J4-Pad5)") (class "Default")
      (node (ref "J4") (pin "5") (pinfunction "5_5") (pintype "passive"))
    )
    (net (code "95") (name "unconnected-(J4-Pad8)") (class "Default")
      (node (ref "J4") (pin "8") (pinfunction "8_8") (pintype "passive"))
    )
    (net (code "96") (name "unconnected-(U1-AIN0.0-Pad18)") (class "Default")
      (node (ref "U1") (pin "18") (pinfunction "AIN0.0_18") (pintype "passive"))
    )
    (net (code "97") (name "unconnected-(U1-AIN0.1-Pad19)") (class "Default")
      (node (ref "U1") (pin "19") (pinfunction "AIN0.1_19") (pintype "passive"))
    )
    (net (code "98") (name "unconnected-(U1-AIN0.2-Pad20)") (class "Default")
      (node (ref "U1") (pin "20") (pinfunction "AIN0.2_20") (pintype "passive"))
    )
    (net (code "99") (name "unconnected-(U1-AIN0.3-Pad21)") (class "Default")
      (node (ref "U1") (pin "21") (pinfunction "AIN0.3_21") (pintype "passive"))
    )
    (net (code "100") (name "unconnected-(U1-AIN0.4-Pad22)") (class "Default")
      (node (ref "U1") (pin "22") (pinfunction "AIN0.4_22") (pintype "passive"))
    )
    (net (code "101") (name "unconnected-(U1-AIN0.5-Pad23)") (class "Default")
      (node (ref "U1") (pin "23") (pinfunction "AIN0.5_23") (pintype "passive"))
    )
    (net (code "102") (name "unconnected-(U1-AIN0.6-Pad24)") (class "Default")
      (node (ref "U1") (pin "24") (pinfunction "AIN0.6_24") (pintype "passive"))
    )
    (net (code "103") (name "unconnected-(U1-AIN0.7-Pad25)") (class "Default")
      (node (ref "U1") (pin "25") (pinfunction "AIN0.7_25") (pintype "passive"))
    )
    (net (code "104") (name "unconnected-(U1-ALE{slash}P0.5-Pad57)") (class "Default")
      (node (ref "U1") (pin "57") (pinfunction "ALE/P0.5_57") (pintype "passive"))
    )
    (net (code "105") (name "unconnected-(U1-CP0+-Pad9)") (class "Default")
      (node (ref "U1") (pin "9") (pinfunction "CP0+_9") (pintype "passive"))
    )
    (net (code "106") (name "unconnected-(U1-CP0--Pad8)") (class "Default")
      (node (ref "U1") (pin "8") (pinfunction "CP0-_8") (pintype "passive"))
    )
    (net (code "107") (name "unconnected-(U1-CP1+-Pad7)") (class "Default")
      (node (ref "U1") (pin "7") (pinfunction "CP1+_7") (pintype "passive"))
    )
    (net (code "108") (name "unconnected-(U1-CP1--Pad6)") (class "Default")
      (node (ref "U1") (pin "6") (pinfunction "CP1-_6") (pintype "passive"))
    )
    (net (code "109") (name "unconnected-(U1-DAC0-Pad100)") (class "Default")
      (node (ref "U1") (pin "100") (pinfunction "DAC0_100") (pintype "passive"))
    )
    (net (code "110") (name "unconnected-(U1-DAC1-Pad99)") (class "Default")
      (node (ref "U1") (pin "99") (pinfunction "DAC1_99") (pintype "passive"))
    )
    (net (code "111") (name "unconnected-(U1-P0.0-Pad62)") (class "Default")
      (node (ref "U1") (pin "62") (pinfunction "P0.0_62") (pintype "passive"))
    )
    (net (code "112") (name "unconnected-(U1-P0.1-Pad61)") (class "Default")
      (node (ref "U1") (pin "61") (pinfunction "P0.1_61") (pintype "passive"))
    )
    (net (code "113") (name "unconnected-(U1-P2.0-Pad46)") (class "Default")
      (node (ref "U1") (pin "46") (pinfunction "P2.0_46") (pintype "passive"))
    )
    (net (code "114") (name "unconnected-(U1-P2.1-Pad45)") (class "Default")
      (node (ref "U1") (pin "45") (pinfunction "P2.1_45") (pintype "passive"))
    )
    (net (code "115") (name "unconnected-(U1-P2.2-Pad44)") (class "Default")
      (node (ref "U1") (pin "44") (pinfunction "P2.2_44") (pintype "passive"))
    )
    (net (code "116") (name "unconnected-(U1-P2.3-Pad43)") (class "Default")
      (node (ref "U1") (pin "43") (pinfunction "P2.3_43") (pintype "passive"))
    )
    (net (code "117") (name "unconnected-(U1-P2.4-Pad42)") (class "Default")
      (node (ref "U1") (pin "42") (pinfunction "P2.4_42") (pintype "passive"))
    )
    (net (code "118") (name "unconnected-(U1-P2.5-Pad41)") (class "Default")
      (node (ref "U1") (pin "41") (pinfunction "P2.5_41") (pintype "passive"))
    )
    (net (code "119") (name "unconnected-(U1-P2.6-Pad40)") (class "Default")
      (node (ref "U1") (pin "40") (pinfunction "P2.6_40") (pintype "passive"))
    )
    (net (code "120") (name "unconnected-(U1-P2.7-Pad39)") (class "Default")
      (node (ref "U1") (pin "39") (pinfunction "P2.7_39") (pintype "passive"))
    )
    (net (code "121") (name "unconnected-(U1-P3.0-Pad54)") (class "Default")
      (node (ref "U1") (pin "54") (pinfunction "P3.0_54") (pintype "passive"))
    )
    (net (code "122") (name "unconnected-(U1-P3.1-Pad53)") (class "Default")
      (node (ref "U1") (pin "53") (pinfunction "P3.1_53") (pintype "passive"))
    )
    (net (code "123") (name "unconnected-(U1-P3.2-Pad52)") (class "Default")
      (node (ref "U1") (pin "52") (pinfunction "P3.2_52") (pintype "passive"))
    )
    (net (code "124") (name "unconnected-(U1-P3.3-Pad51)") (class "Default")
      (node (ref "U1") (pin "51") (pinfunction "P3.3_51") (pintype "passive"))
    )
    (net (code "125") (name "unconnected-(U1-P3.4-Pad50)") (class "Default")
      (node (ref "U1") (pin "50") (pinfunction "P3.4_50") (pintype "passive"))
    )
    (net (code "126") (name "unconnected-(U1-P3.5-Pad49)") (class "Default")
      (node (ref "U1") (pin "49") (pinfunction "P3.5_49") (pintype "passive"))
    )
    (net (code "127") (name "unconnected-(U1-P3.6-Pad48)") (class "Default")
      (node (ref "U1") (pin "48") (pinfunction "P3.6_48") (pintype "passive"))
    )
    (net (code "128") (name "unconnected-(U1-P3.7-Pad47)") (class "Default")
      (node (ref "U1") (pin "47") (pinfunction "P3.7_47") (pintype "passive"))
    )
    (net (code "129") (name "unconnected-(U1-VREF-Pad12)") (class "Default")
      (node (ref "U1") (pin "12") (pinfunction "VREF_12") (pintype "passive"))
    )
    (net (code "130") (name "unconnected-(U1-VREF0-Pad16)") (class "Default")
      (node (ref "U1") (pin "16") (pinfunction "VREF0_16") (pintype "passive"))
    )
    (net (code "131") (name "unconnected-(U1-VREF1-Pad17)") (class "Default")
      (node (ref "U1") (pin "17") (pinfunction "VREF1_17") (pintype "passive"))
    )
    (net (code "132") (name "unconnected-(U1-VREFD-Pad15)") (class "Default")
      (node (ref "U1") (pin "15") (pinfunction "VREFD_15") (pintype "passive"))
    )
  )
)
